# 2_disp.net
KiCad netlist of a schematic drawn in EAGLE
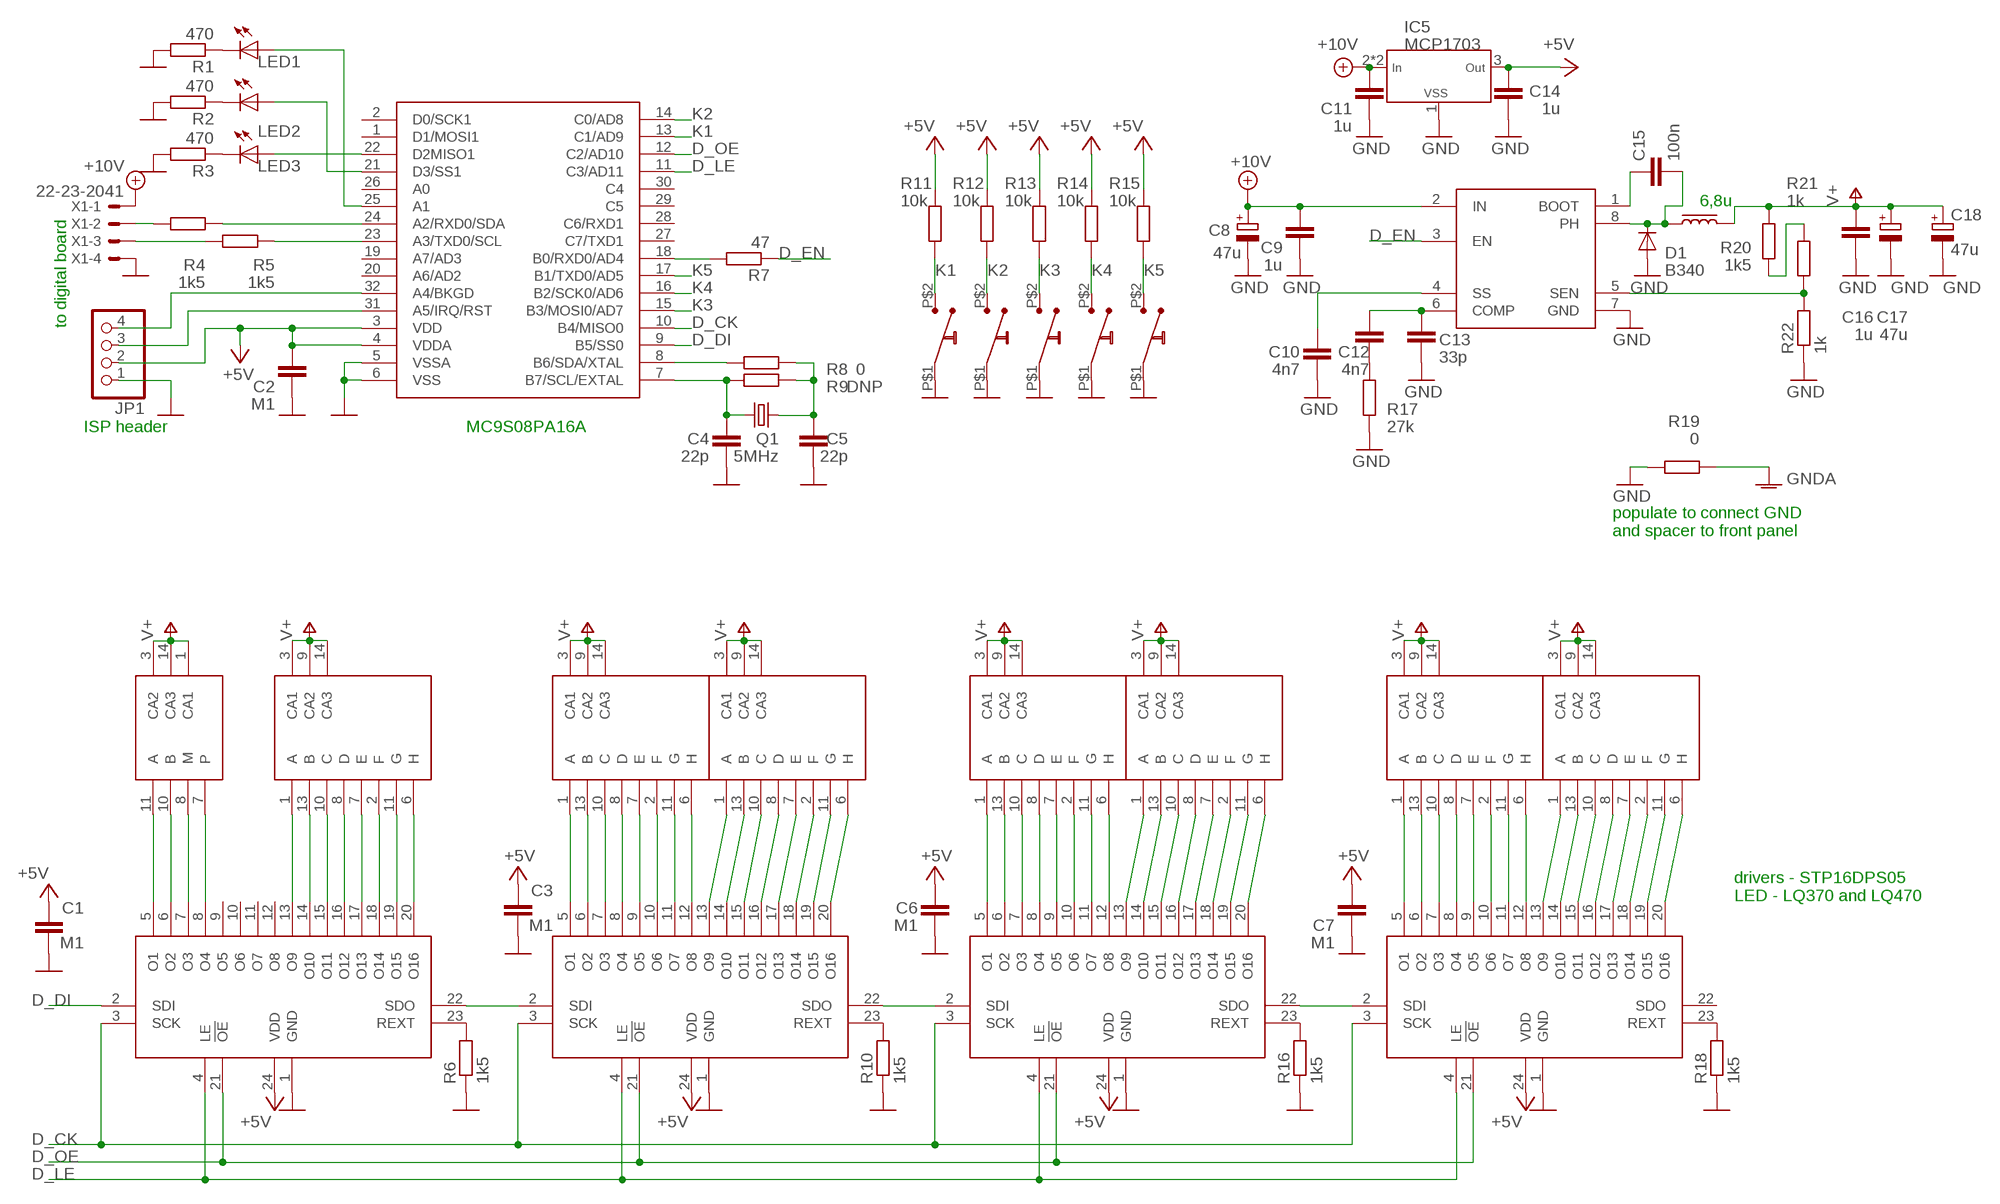
[diagram p0: schematic, sheet 1]

(export (version "E")
  (design (tool "Eeschema 10.0.6"))
  (components
    (comp (ref "C1")
      (value "M1")
      (footprint "eagle-import:R0805")
      (libsource (lib "eagle-import") (part "C_0806"))
    )
    (comp (ref "C2")
      (value "M1")
      (footprint "eagle-import:R0805")
      (libsource (lib "eagle-import") (part "C_0806"))
    )
    (comp (ref "C3")
      (value "M1")
      (footprint "eagle-import:R0805")
      (libsource (lib "eagle-import") (part "C_0806"))
    )
    (comp (ref "C4")
      (value "22p")
      (footprint "eagle-import:R0805")
      (libsource (lib "eagle-import") (part "C_0806"))
    )
    (comp (ref "C5")
      (value "22p")
      (footprint "eagle-import:R0805")
      (libsource (lib "eagle-import") (part "C_0806"))
    )
    (comp (ref "C6")
      (value "M1")
      (footprint "eagle-import:R0805")
      (libsource (lib "eagle-import") (part "C_0806"))
    )
    (comp (ref "C7")
      (value "M1")
      (footprint "eagle-import:R0805")
      (libsource (lib "eagle-import") (part "C_0806"))
    )
    (comp (ref "C8")
      (value "47u")
      (footprint "eagle-import:SMC_C")
      (libsource (lib "eagle-import") (part "CPOL-EUSMCC"))
    )
    (comp (ref "C9")
      (value "1u")
      (footprint "eagle-import:R0805")
      (libsource (lib "eagle-import") (part "C_0806"))
    )
    (comp (ref "C10")
      (value "4n7")
      (footprint "eagle-import:R0805")
      (libsource (lib "eagle-import") (part "C_0806"))
    )
    (comp (ref "C11")
      (value "1u")
      (footprint "eagle-import:R0805")
      (libsource (lib "eagle-import") (part "C_0806"))
    )
    (comp (ref "C12")
      (value "4n7")
      (footprint "eagle-import:R0805")
      (libsource (lib "eagle-import") (part "C_0806"))
    )
    (comp (ref "C13")
      (value "33p")
      (footprint "eagle-import:R0805")
      (libsource (lib "eagle-import") (part "C_0806"))
    )
    (comp (ref "C14")
      (value "1u")
      (footprint "eagle-import:R0805")
      (libsource (lib "eagle-import") (part "C_0806"))
    )
    (comp (ref "C15")
      (value "100n")
      (footprint "eagle-import:R0805")
      (libsource (lib "eagle-import") (part "C_0806"))
    )
    (comp (ref "C16")
      (value "1u")
      (footprint "eagle-import:R0805")
      (libsource (lib "eagle-import") (part "C_0806"))
    )
    (comp (ref "C17")
      (value "47u")
      (footprint "eagle-import:SMC_C")
      (libsource (lib "eagle-import") (part "CPOL-EUSMCC"))
    )
    (comp (ref "C18")
      (value "47u")
      (footprint "eagle-import:SMC_C")
      (libsource (lib "eagle-import") (part "CPOL-EUSMCC"))
    )
    (comp (ref "D1")
      (value "B340")
      (footprint "eagle-import:SMB")
      (libsource (lib "eagle-import") (part "DIODE-SMB"))
    )
    (comp (ref "DI1")
      (value "LQ3XX")
      (footprint "eagle-import:LQ_DISP")
      (libsource (lib "eagle-import") (part "LQ3XX"))
    )
    (comp (ref "DI2")
      (value "LQ4XX")
      (footprint "eagle-import:LQ_DISP")
      (libsource (lib "eagle-import") (part "LQ4XX"))
    )
    (comp (ref "DI3")
      (value "LQ4XX")
      (footprint "eagle-import:LQ_DISP")
      (libsource (lib "eagle-import") (part "LQ4XX"))
    )
    (comp (ref "DI4")
      (value "LQ4XX")
      (footprint "eagle-import:LQ_DISP")
      (libsource (lib "eagle-import") (part "LQ4XX"))
    )
    (comp (ref "DI5")
      (value "LQ4XX")
      (footprint "eagle-import:LQ_DISP")
      (libsource (lib "eagle-import") (part "LQ4XX"))
    )
    (comp (ref "DI6")
      (value "LQ4XX")
      (footprint "eagle-import:LQ_DISP")
      (libsource (lib "eagle-import") (part "LQ4XX"))
    )
    (comp (ref "DI7")
      (value "LQ4XX")
      (footprint "eagle-import:LQ_DISP")
      (libsource (lib "eagle-import") (part "LQ4XX"))
    )
    (comp (ref "DI8")
      (value "LQ4XX")
      (footprint "eagle-import:LQ_DISP")
      (libsource (lib "eagle-import") (part "LQ4XX"))
    )
    (comp (ref "IC1")
      (value "STP16CPS05")
      (footprint "eagle-import:QSOP24")
      (libsource (lib "eagle-import") (part "STP16CPS05"))
    )
    (comp (ref "IC2")
      (value "MC9S08PT60TQ32")
      (footprint "eagle-import:TQFP32-8")
      (libsource (lib "eagle-import") (part "MC9S08PT60TQ32"))
    )
    (comp (ref "IC3")
      (value "STP16CPS05")
      (footprint "eagle-import:QSOP24")
      (libsource (lib "eagle-import") (part "STP16CPS05"))
    )
    (comp (ref "IC4")
      (value "STP16CPS05")
      (footprint "eagle-import:QSOP24")
      (libsource (lib "eagle-import") (part "STP16CPS05"))
    )
    (comp (ref "IC5")
      (value "MCP1703")
      (footprint "eagle-import:SOT89")
      (libsource (lib "eagle-import") (part "MCP1702-SOT89"))
    )
    (comp (ref "IC6")
      (value "STP16CPS05")
      (footprint "eagle-import:QSOP24")
      (libsource (lib "eagle-import") (part "STP16CPS05"))
    )
    (comp (ref "IC7")
      (value "TPS54331")
      (footprint "eagle-import:SO-08")
      (libsource (lib "eagle-import") (part "TPS54331"))
    )
    (comp (ref "JP1")
      (value "PINHD-1X04_2.54")
      (footprint "eagle-import:1X04")
      (libsource (lib "eagle-import") (part "PINHD-1X04_2.54"))
    )
    (comp (ref "K1")
      (value "SWITCH_MINI6450")
      (footprint "eagle-import:SWITCH_6450")
      (libsource (lib "eagle-import") (part "SWITCH_MINI6450"))
    )
    (comp (ref "K2")
      (value "SWITCH_MINI6450")
      (footprint "eagle-import:SWITCH_6450")
      (libsource (lib "eagle-import") (part "SWITCH_MINI6450"))
    )
    (comp (ref "K3")
      (value "SWITCH_MINI6450")
      (footprint "eagle-import:SWITCH_6450")
      (libsource (lib "eagle-import") (part "SWITCH_MINI6450"))
    )
    (comp (ref "K4")
      (value "SWITCH_MINI6450")
      (footprint "eagle-import:SWITCH_6450")
      (libsource (lib "eagle-import") (part "SWITCH_MINI6450"))
    )
    (comp (ref "K5")
      (value "SWITCH_MINI6450")
      (footprint "eagle-import:SWITCH_6450")
      (libsource (lib "eagle-import") (part "SWITCH_MINI6450"))
    )
    (comp (ref "L1")
      (value "SRP7030")
      (footprint "eagle-import:BOURNS_SRP7030")
      (libsource (lib "eagle-import") (part "INDUCTORBOURNS_SRP7030"))
    )
    (comp (ref "LED1")
      (value "LEDCHIPLED_0805")
      (footprint "eagle-import:CHIPLED_0805")
      (libsource (lib "eagle-import") (part "LEDCHIPLED_0805"))
    )
    (comp (ref "LED2")
      (value "LEDCHIPLED_1206")
      (footprint "eagle-import:CHIPLED_1206")
      (libsource (lib "eagle-import") (part "LEDCHIPLED_1206"))
    )
    (comp (ref "LED3")
      (value "LEDCHIPLED_1206")
      (footprint "eagle-import:CHIPLED_1206")
      (libsource (lib "eagle-import") (part "LEDCHIPLED_1206"))
    )
    (comp (ref "Q1")
      (value "5MHz")
      (footprint "eagle-import:TC38H")
      (libsource (lib "eagle-import") (part "CRYSTALTC38H"))
    )
    (comp (ref "R1")
      (value "470")
      (footprint "eagle-import:R0805")
      (libsource (lib "eagle-import") (part "R_0805"))
    )
    (comp (ref "R2")
      (value "470")
      (footprint "eagle-import:R0805")
      (libsource (lib "eagle-import") (part "R_0805"))
    )
    (comp (ref "R3")
      (value "470")
      (footprint "eagle-import:R0805")
      (libsource (lib "eagle-import") (part "R_0805"))
    )
    (comp (ref "R4")
      (value "1k5")
      (footprint "eagle-import:R0805")
      (libsource (lib "eagle-import") (part "R_0805"))
    )
    (comp (ref "R5")
      (value "1k5")
      (footprint "eagle-import:R0805")
      (libsource (lib "eagle-import") (part "R_0805"))
    )
    (comp (ref "R6")
      (value "1k5")
      (footprint "eagle-import:R0805")
      (libsource (lib "eagle-import") (part "R_0805"))
    )
    (comp (ref "R7")
      (value "47")
      (footprint "eagle-import:R0805")
      (libsource (lib "eagle-import") (part "R_0805"))
    )
    (comp (ref "R8")
      (value "0")
      (footprint "eagle-import:R0805")
      (libsource (lib "eagle-import") (part "R_0805"))
    )
    (comp (ref "R9")
      (value "DNP")
      (footprint "eagle-import:R0805")
      (libsource (lib "eagle-import") (part "R_0805"))
    )
    (comp (ref "R10")
      (value "1k5")
      (footprint "eagle-import:R0805")
      (libsource (lib "eagle-import") (part "R_0805"))
    )
    (comp (ref "R11")
      (value "10k")
      (footprint "eagle-import:R0805")
      (libsource (lib "eagle-import") (part "R_0805"))
    )
    (comp (ref "R12")
      (value "10k")
      (footprint "eagle-import:R0805")
      (libsource (lib "eagle-import") (part "R_0805"))
    )
    (comp (ref "R13")
      (value "10k")
      (footprint "eagle-import:R0805")
      (libsource (lib "eagle-import") (part "R_0805"))
    )
    (comp (ref "R14")
      (value "10k")
      (footprint "eagle-import:R0805")
      (libsource (lib "eagle-import") (part "R_0805"))
    )
    (comp (ref "R15")
      (value "10k")
      (footprint "eagle-import:R0805")
      (libsource (lib "eagle-import") (part "R_0805"))
    )
    (comp (ref "R16")
      (value "1k5")
      (footprint "eagle-import:R0805")
      (libsource (lib "eagle-import") (part "R_0805"))
    )
    (comp (ref "R17")
      (value "27k")
      (footprint "eagle-import:R0805")
      (libsource (lib "eagle-import") (part "R_0805"))
    )
    (comp (ref "R18")
      (value "1k5")
      (footprint "eagle-import:R0805")
      (libsource (lib "eagle-import") (part "R_0805"))
    )
    (comp (ref "R19")
      (value "0")
      (footprint "eagle-import:R0805")
      (libsource (lib "eagle-import") (part "R_0805"))
    )
    (comp (ref "R20")
      (value "1k5")
      (footprint "eagle-import:R0805")
      (libsource (lib "eagle-import") (part "R_0805"))
    )
    (comp (ref "R21")
      (value "1k")
      (footprint "eagle-import:R0805")
      (libsource (lib "eagle-import") (part "R_0805"))
    )
    (comp (ref "R22")
      (value "1k")
      (footprint "eagle-import:R0805")
      (libsource (lib "eagle-import") (part "R_0805"))
    )
    (comp (ref "X1")
      (value "22-23-2041")
      (footprint "eagle-import:22-23-2041")
      (fields (field (name "MF") "MOLEX"))
      (libsource (lib "eagle-import") (part "22-23-2041"))
    )
  )
  (nets
    (net (code "1") (name "+5V") (class "Default")
      (node (ref "C1") (pin "2") (pinfunction "2_2") (pintype "passive"))
      (node (ref "C14") (pin "2") (pinfunction "2_2") (pintype "passive"))
      (node (ref "C2") (pin "2") (pinfunction "2_2") (pintype "passive"))
      (node (ref "C3") (pin "2") (pinfunction "2_2") (pintype "passive"))
      (node (ref "C6") (pin "2") (pinfunction "2_2") (pintype "passive"))
      (node (ref "C7") (pin "2") (pinfunction "2_2") (pintype "passive"))
      (node (ref "IC1") (pin "24") (pinfunction "VDD_24") (pintype "bidirectional"))
      (node (ref "IC2") (pin "3") (pinfunction "VDD_3") (pintype "bidirectional"))
      (node (ref "IC2") (pin "4") (pinfunction "VDDA_4") (pintype "bidirectional"))
      (node (ref "IC3") (pin "24") (pinfunction "VDD_24") (pintype "bidirectional"))
      (node (ref "IC4") (pin "24") (pinfunction "VDD_24") (pintype "bidirectional"))
      (node (ref "IC5") (pin "3") (pinfunction "OUT_3") (pintype "output"))
      (node (ref "IC6") (pin "24") (pinfunction "VDD_24") (pintype "bidirectional"))
      (node (ref "JP1") (pin "2") (pinfunction "2_2") (pintype "passive"))
      (node (ref "R11") (pin "1") (pinfunction "1_1") (pintype "passive"))
      (node (ref "R12") (pin "1") (pinfunction "1_1") (pintype "passive"))
      (node (ref "R13") (pin "1") (pinfunction "1_1") (pintype "passive"))
      (node (ref "R14") (pin "1") (pinfunction "1_1") (pintype "passive"))
      (node (ref "R15") (pin "1") (pinfunction "1_1") (pintype "passive"))
    )
    (net (code "2") (name "+10V") (class "Default")
      (node (ref "C11") (pin "2") (pinfunction "2_2") (pintype "passive"))
      (node (ref "C8") (pin "+") (pinfunction "+_+") (pintype "passive"))
      (node (ref "C9") (pin "2") (pinfunction "2_2") (pintype "passive"))
      (node (ref "IC5") (pin "2") (pinfunction "IN_2") (pintype "input"))
      (node (ref "IC5") (pin "2@1") (pinfunction "IN_2@1") (pintype "input"))
      (node (ref "IC7") (pin "2") (pinfunction "IN_2") (pintype "bidirectional"))
      (node (ref "X1") (pin "1") (pinfunction "S_1") (pintype "passive"))
    )
    (net (code "3") (name "/D_CK") (class "Default")
      (node (ref "IC1") (pin "3") (pinfunction "SCK_3") (pintype "bidirectional"))
      (node (ref "IC2") (pin "10") (pinfunction "B4/MISO0_10") (pintype "bidirectional"))
      (node (ref "IC3") (pin "3") (pinfunction "SCK_3") (pintype "bidirectional"))
      (node (ref "IC4") (pin "3") (pinfunction "SCK_3") (pintype "bidirectional"))
      (node (ref "IC6") (pin "3") (pinfunction "SCK_3") (pintype "bidirectional"))
    )
    (net (code "4") (name "/D_DI") (class "Default")
      (node (ref "IC1") (pin "2") (pinfunction "SDI_2") (pintype "bidirectional"))
      (node (ref "IC2") (pin "9") (pinfunction "B5/SS0_9") (pintype "bidirectional"))
    )
    (net (code "5") (name "/D_EN") (class "Default")
      (node (ref "IC7") (pin "3") (pinfunction "EN_3") (pintype "bidirectional"))
      (node (ref "R7") (pin "1") (pinfunction "1_1") (pintype "passive"))
    )
    (net (code "6") (name "/D_LE") (class "Default")
      (node (ref "IC1") (pin "4") (pinfunction "LE_4") (pintype "bidirectional"))
      (node (ref "IC2") (pin "11") (pinfunction "C3/AD11_11") (pintype "bidirectional"))
      (node (ref "IC3") (pin "4") (pinfunction "LE_4") (pintype "bidirectional"))
      (node (ref "IC4") (pin "4") (pinfunction "LE_4") (pintype "bidirectional"))
      (node (ref "IC6") (pin "4") (pinfunction "LE_4") (pintype "bidirectional"))
    )
    (net (code "7") (name "/D_OE") (class "Default")
      (node (ref "IC1") (pin "21") (pinfunction "~{OE}_21") (pintype "bidirectional"))
      (node (ref "IC2") (pin "12") (pinfunction "C2/AD10_12") (pintype "bidirectional"))
      (node (ref "IC3") (pin "21") (pinfunction "~{OE}_21") (pintype "bidirectional"))
      (node (ref "IC4") (pin "21") (pinfunction "~{OE}_21") (pintype "bidirectional"))
      (node (ref "IC6") (pin "21") (pinfunction "~{OE}_21") (pintype "bidirectional"))
    )
    (net (code "8") (name "/K1") (class "Default")
      (node (ref "IC2") (pin "13") (pinfunction "C1/AD9_13") (pintype "bidirectional"))
      (node (ref "K1") (pin "P$2") (pinfunction "P$2_P$2") (pintype "bidirectional"))
      (node (ref "R11") (pin "2") (pinfunction "2_2") (pintype "passive"))
    )
    (net (code "9") (name "/K2") (class "Default")
      (node (ref "IC2") (pin "14") (pinfunction "C0/AD8_14") (pintype "bidirectional"))
      (node (ref "K2") (pin "P$2") (pinfunction "P$2_P$2") (pintype "bidirectional"))
      (node (ref "R12") (pin "2") (pinfunction "2_2") (pintype "passive"))
    )
    (net (code "10") (name "/K3") (class "Default")
      (node (ref "IC2") (pin "15") (pinfunction "B3/MOSI0/AD7_15") (pintype "bidirectional"))
      (node (ref "K3") (pin "P$2") (pinfunction "P$2_P$2") (pintype "bidirectional"))
      (node (ref "R13") (pin "2") (pinfunction "2_2") (pintype "passive"))
    )
    (net (code "11") (name "/K4") (class "Default")
      (node (ref "IC2") (pin "16") (pinfunction "B2/SCK0/AD6_16") (pintype "bidirectional"))
      (node (ref "K4") (pin "P$2") (pinfunction "P$2_P$2") (pintype "bidirectional"))
      (node (ref "R14") (pin "2") (pinfunction "2_2") (pintype "passive"))
    )
    (net (code "12") (name "/K5") (class "Default")
      (node (ref "IC2") (pin "17") (pinfunction "B1/TXD0/AD5_17") (pintype "bidirectional"))
      (node (ref "K5") (pin "P$2") (pinfunction "P$2_P$2") (pintype "bidirectional"))
      (node (ref "R15") (pin "2") (pinfunction "2_2") (pintype "passive"))
    )
    (net (code "13") (name "GND") (class "Default")
      (node (ref "C1") (pin "1") (pinfunction "1_1") (pintype "passive"))
      (node (ref "C10") (pin "1") (pinfunction "1_1") (pintype "passive"))
      (node (ref "C11") (pin "1") (pinfunction "1_1") (pintype "passive"))
      (node (ref "C13") (pin "1") (pinfunction "1_1") (pintype "passive"))
      (node (ref "C14") (pin "1") (pinfunction "1_1") (pintype "passive"))
      (node (ref "C16") (pin "1") (pinfunction "1_1") (pintype "passive"))
      (node (ref "C17") (pin "-") (pinfunction "-_-") (pintype "passive"))
      (node (ref "C18") (pin "-") (pinfunction "-_-") (pintype "passive"))
      (node (ref "C2") (pin "1") (pinfunction "1_1") (pintype "passive"))
      (node (ref "C3") (pin "1") (pinfunction "1_1") (pintype "passive"))
      (node (ref "C4") (pin "1") (pinfunction "1_1") (pintype "passive"))
      (node (ref "C5") (pin "1") (pinfunction "1_1") (pintype "passive"))
      (node (ref "C6") (pin "1") (pinfunction "1_1") (pintype "passive"))
      (node (ref "C7") (pin "1") (pinfunction "1_1") (pintype "passive"))
      (node (ref "C8") (pin "-") (pinfunction "-_-") (pintype "passive"))
      (node (ref "C9") (pin "1") (pinfunction "1_1") (pintype "passive"))
      (node (ref "D1") (pin "A") (pinfunction "A_A") (pintype "passive"))
      (node (ref "IC1") (pin "1") (pinfunction "GND_1") (pintype "bidirectional"))
      (node (ref "IC2") (pin "5") (pinfunction "VSSA_5") (pintype "bidirectional"))
      (node (ref "IC2") (pin "6") (pinfunction "VSS_6") (pintype "bidirectional"))
      (node (ref "IC3") (pin "1") (pinfunction "GND_1") (pintype "bidirectional"))
      (node (ref "IC4") (pin "1") (pinfunction "GND_1") (pintype "bidirectional"))
      (node (ref "IC5") (pin "1") (pinfunction "VSS_1") (pintype "input"))
      (node (ref "IC6") (pin "1") (pinfunction "GND_1") (pintype "bidirectional"))
      (node (ref "IC7") (pin "7") (pinfunction "GND_7") (pintype "bidirectional"))
      (node (ref "JP1") (pin "1") (pinfunction "1_1") (pintype "passive"))
      (node (ref "K1") (pin "P$1") (pinfunction "P$1_P$1") (pintype "bidirectional"))
      (node (ref "K2") (pin "P$1") (pinfunction "P$1_P$1") (pintype "bidirectional"))
      (node (ref "K3") (pin "P$1") (pinfunction "P$1_P$1") (pintype "bidirectional"))
      (node (ref "K4") (pin "P$1") (pinfunction "P$1_P$1") (pintype "bidirectional"))
      (node (ref "K5") (pin "P$1") (pinfunction "P$1_P$1") (pintype "bidirectional"))
      (node (ref "R1") (pin "2") (pinfunction "2_2") (pintype "passive"))
      (node (ref "R10") (pin "1") (pinfunction "1_1") (pintype "passive"))
      (node (ref "R16") (pin "1") (pinfunction "1_1") (pintype "passive"))
      (node (ref "R17") (pin "1") (pinfunction "1_1") (pintype "passive"))
      (node (ref "R18") (pin "1") (pinfunction "1_1") (pintype "passive"))
      (node (ref "R19") (pin "2") (pinfunction "2_2") (pintype "passive"))
      (node (ref "R2") (pin "2") (pinfunction "2_2") (pintype "passive"))
      (node (ref "R22") (pin "1") (pinfunction "1_1") (pintype "passive"))
      (node (ref "R3") (pin "2") (pinfunction "2_2") (pintype "passive"))
      (node (ref "R6") (pin "1") (pinfunction "1_1") (pintype "passive"))
      (node (ref "X1") (pin "4") (pinfunction "S_4") (pintype "passive"))
    )
    (net (code "14") (name "GNDA") (class "Default")
      (node (ref "R19") (pin "1") (pinfunction "1_1") (pintype "passive"))
    )
    (net (code "15") (name "Net-(C5-Pad2)") (class "Default")
      (node (ref "C5") (pin "2") (pinfunction "2_2") (pintype "passive"))
      (node (ref "Q1") (pin "1") (pinfunction "1_1") (pintype "passive"))
      (node (ref "R8") (pin "1") (pinfunction "1_1") (pintype "passive"))
      (node (ref "R9") (pin "1") (pinfunction "1_1") (pintype "passive"))
    )
    (net (code "16") (name "Net-(C12-Pad1)") (class "Default")
      (node (ref "C12") (pin "1") (pinfunction "1_1") (pintype "passive"))
      (node (ref "R17") (pin "2") (pinfunction "2_2") (pintype "passive"))
    )
    (net (code "17") (name "Net-(DI1-A)") (class "Default")
      (node (ref "DI1") (pin "11") (pinfunction "A_11") (pintype "bidirectional"))
      (node (ref "IC1") (pin "5") (pinfunction "O1_5") (pintype "bidirectional"))
    )
    (net (code "18") (name "Net-(DI1-B)") (class "Default")
      (node (ref "DI1") (pin "10") (pinfunction "B_10") (pintype "bidirectional"))
      (node (ref "IC1") (pin "6") (pinfunction "O2_6") (pintype "bidirectional"))
    )
    (net (code "19") (name "Net-(DI1-M)") (class "Default")
      (node (ref "DI1") (pin "8") (pinfunction "M_8") (pintype "bidirectional"))
      (node (ref "IC1") (pin "7") (pinfunction "O3_7") (pintype "bidirectional"))
    )
    (net (code "20") (name "Net-(DI1-P)") (class "Default")
      (node (ref "DI1") (pin "7") (pinfunction "P_7") (pintype "bidirectional"))
      (node (ref "IC1") (pin "8") (pinfunction "O4_8") (pintype "bidirectional"))
    )
    (net (code "21") (name "Net-(DI2-A)") (class "Default")
      (node (ref "DI2") (pin "1") (pinfunction "A_1") (pintype "bidirectional"))
      (node (ref "IC1") (pin "13") (pinfunction "O9_13") (pintype "bidirectional"))
    )
    (net (code "22") (name "Net-(DI2-B)") (class "Default")
      (node (ref "DI2") (pin "13") (pinfunction "B_13") (pintype "bidirectional"))
      (node (ref "IC1") (pin "14") (pinfunction "O10_14") (pintype "bidirectional"))
    )
    (net (code "23") (name "Net-(DI2-C)") (class "Default")
      (node (ref "DI2") (pin "10") (pinfunction "C_10") (pintype "bidirectional"))
      (node (ref "IC1") (pin "15") (pinfunction "O11_15") (pintype "bidirectional"))
    )
    (net (code "24") (name "Net-(DI2-D)") (class "Default")
      (node (ref "DI2") (pin "8") (pinfunction "D_8") (pintype "bidirectional"))
      (node (ref "IC1") (pin "16") (pinfunction "O12_16") (pintype "bidirectional"))
    )
    (net (code "25") (name "Net-(DI2-E)") (class "Default")
      (node (ref "DI2") (pin "7") (pinfunction "E_7") (pintype "bidirectional"))
      (node (ref "IC1") (pin "17") (pinfunction "O13_17") (pintype "bidirectional"))
    )
    (net (code "26") (name "Net-(DI2-F)") (class "Default")
      (node (ref "DI2") (pin "2") (pinfunction "F_2") (pintype "bidirectional"))
      (node (ref "IC1") (pin "18") (pinfunction "O14_18") (pintype "bidirectional"))
    )
    (net (code "27") (name "Net-(DI2-G)") (class "Default")
      (node (ref "DI2") (pin "11") (pinfunction "G_11") (pintype "bidirectional"))
      (node (ref "IC1") (pin "19") (pinfunction "O15_19") (pintype "bidirectional"))
    )
    (net (code "28") (name "Net-(DI2-H)") (class "Default")
      (node (ref "DI2") (pin "6") (pinfunction "H_6") (pintype "bidirectional"))
      (node (ref "IC1") (pin "20") (pinfunction "O16_20") (pintype "bidirectional"))
    )
    (net (code "29") (name "Net-(DI3-A)") (class "Default")
      (node (ref "DI3") (pin "1") (pinfunction "A_1") (pintype "bidirectional"))
      (node (ref "IC3") (pin "5") (pinfunction "O1_5") (pintype "bidirectional"))
    )
    (net (code "30") (name "Net-(DI3-B)") (class "Default")
      (node (ref "DI3") (pin "13") (pinfunction "B_13") (pintype "bidirectional"))
      (node (ref "IC3") (pin "6") (pinfunction "O2_6") (pintype "bidirectional"))
    )
    (net (code "31") (name "Net-(DI3-C)") (class "Default")
      (node (ref "DI3") (pin "10") (pinfunction "C_10") (pintype "bidirectional"))
      (node (ref "IC3") (pin "7") (pinfunction "O3_7") (pintype "bidirectional"))
    )
    (net (code "32") (name "Net-(DI3-D)") (class "Default")
      (node (ref "DI3") (pin "8") (pinfunction "D_8") (pintype "bidirectional"))
      (node (ref "IC3") (pin "8") (pinfunction "O4_8") (pintype "bidirectional"))
    )
    (net (code "33") (name "Net-(DI3-E)") (class "Default")
      (node (ref "DI3") (pin "7") (pinfunction "E_7") (pintype "bidirectional"))
      (node (ref "IC3") (pin "9") (pinfunction "O5_9") (pintype "bidirectional"))
    )
    (net (code "34") (name "Net-(DI3-F)") (class "Default")
      (node (ref "DI3") (pin "2") (pinfunction "F_2") (pintype "bidirectional"))
      (node (ref "IC3") (pin "10") (pinfunction "O6_10") (pintype "bidirectional"))
    )
    (net (code "35") (name "Net-(DI3-G)") (class "Default")
      (node (ref "DI3") (pin "11") (pinfunction "G_11") (pintype "bidirectional"))
      (node (ref "IC3") (pin "11") (pinfunction "O7_11") (pintype "bidirectional"))
    )
    (net (code "36") (name "Net-(DI3-H)") (class "Default")
      (node (ref "DI3") (pin "6") (pinfunction "H_6") (pintype "bidirectional"))
      (node (ref "IC3") (pin "12") (pinfunction "O8_12") (pintype "bidirectional"))
    )
    (net (code "37") (name "Net-(DI4-A)") (class "Default")
      (node (ref "DI4") (pin "1") (pinfunction "A_1") (pintype "bidirectional"))
      (node (ref "IC3") (pin "13") (pinfunction "O9_13") (pintype "bidirectional"))
    )
    (net (code "38") (name "Net-(DI4-B)") (class "Default")
      (node (ref "DI4") (pin "13") (pinfunction "B_13") (pintype "bidirectional"))
      (node (ref "IC3") (pin "14") (pinfunction "O10_14") (pintype "bidirectional"))
    )
    (net (code "39") (name "Net-(DI4-C)") (class "Default")
      (node (ref "DI4") (pin "10") (pinfunction "C_10") (pintype "bidirectional"))
      (node (ref "IC3") (pin "15") (pinfunction "O11_15") (pintype "bidirectional"))
    )
    (net (code "40") (name "Net-(DI4-D)") (class "Default")
      (node (ref "DI4") (pin "8") (pinfunction "D_8") (pintype "bidirectional"))
      (node (ref "IC3") (pin "16") (pinfunction "O12_16") (pintype "bidirectional"))
    )
    (net (code "41") (name "Net-(DI4-E)") (class "Default")
      (node (ref "DI4") (pin "7") (pinfunction "E_7") (pintype "bidirectional"))
      (node (ref "IC3") (pin "17") (pinfunction "O13_17") (pintype "bidirectional"))
    )
    (net (code "42") (name "Net-(DI4-F)") (class "Default")
      (node (ref "DI4") (pin "2") (pinfunction "F_2") (pintype "bidirectional"))
      (node (ref "IC3") (pin "18") (pinfunction "O14_18") (pintype "bidirectional"))
    )
    (net (code "43") (name "Net-(DI4-G)") (class "Default")
      (node (ref "DI4") (pin "11") (pinfunction "G_11") (pintype "bidirectional"))
      (node (ref "IC3") (pin "19") (pinfunction "O15_19") (pintype "bidirectional"))
    )
    (net (code "44") (name "Net-(DI4-H)") (class "Default")
      (node (ref "DI4") (pin "6") (pinfunction "H_6") (pintype "bidirectional"))
      (node (ref "IC3") (pin "20") (pinfunction "O16_20") (pintype "bidirectional"))
    )
    (net (code "45") (name "Net-(DI5-A)") (class "Default")
      (node (ref "DI5") (pin "1") (pinfunction "A_1") (pintype "bidirectional"))
      (node (ref "IC4") (pin "5") (pinfunction "O1_5") (pintype "bidirectional"))
    )
    (net (code "46") (name "Net-(DI5-B)") (class "Default")
      (node (ref "DI5") (pin "13") (pinfunction "B_13") (pintype "bidirectional"))
      (node (ref "IC4") (pin "6") (pinfunction "O2_6") (pintype "bidirectional"))
    )
    (net (code "47") (name "Net-(DI5-C)") (class "Default")
      (node (ref "DI5") (pin "10") (pinfunction "C_10") (pintype "bidirectional"))
      (node (ref "IC4") (pin "7") (pinfunction "O3_7") (pintype "bidirectional"))
    )
    (net (code "48") (name "Net-(DI5-D)") (class "Default")
      (node (ref "DI5") (pin "8") (pinfunction "D_8") (pintype "bidirectional"))
      (node (ref "IC4") (pin "8") (pinfunction "O4_8") (pintype "bidirectional"))
    )
    (net (code "49") (name "Net-(DI5-E)") (class "Default")
      (node (ref "DI5") (pin "7") (pinfunction "E_7") (pintype "bidirectional"))
      (node (ref "IC4") (pin "9") (pinfunction "O5_9") (pintype "bidirectional"))
    )
    (net (code "50") (name "Net-(DI5-F)") (class "Default")
      (node (ref "DI5") (pin "2") (pinfunction "F_2") (pintype "bidirectional"))
      (node (ref "IC4") (pin "10") (pinfunction "O6_10") (pintype "bidirectional"))
    )
    (net (code "51") (name "Net-(DI5-G)") (class "Default")
      (node (ref "DI5") (pin "11") (pinfunction "G_11") (pintype "bidirectional"))
      (node (ref "IC4") (pin "11") (pinfunction "O7_11") (pintype "bidirectional"))
    )
    (net (code "52") (name "Net-(DI5-H)") (class "Default")
      (node (ref "DI5") (pin "6") (pinfunction "H_6") (pintype "bidirectional"))
      (node (ref "IC4") (pin "12") (pinfunction "O8_12") (pintype "bidirectional"))
    )
    (net (code "53") (name "Net-(DI6-A)") (class "Default")
      (node (ref "DI6") (pin "1") (pinfunction "A_1") (pintype "bidirectional"))
      (node (ref "IC4") (pin "13") (pinfunction "O9_13") (pintype "bidirectional"))
    )
    (net (code "54") (name "Net-(DI6-B)") (class "Default")
      (node (ref "DI6") (pin "13") (pinfunction "B_13") (pintype "bidirectional"))
      (node (ref "IC4") (pin "14") (pinfunction "O10_14") (pintype "bidirectional"))
    )
    (net (code "55") (name "Net-(DI6-C)") (class "Default")
      (node (ref "DI6") (pin "10") (pinfunction "C_10") (pintype "bidirectional"))
      (node (ref "IC4") (pin "15") (pinfunction "O11_15") (pintype "bidirectional"))
    )
    (net (code "56") (name "Net-(DI6-D)") (class "Default")
      (node (ref "DI6") (pin "8") (pinfunction "D_8") (pintype "bidirectional"))
      (node (ref "IC4") (pin "16") (pinfunction "O12_16") (pintype "bidirectional"))
    )
    (net (code "57") (name "Net-(DI6-E)") (class "Default")
      (node (ref "DI6") (pin "7") (pinfunction "E_7") (pintype "bidirectional"))
      (node (ref "IC4") (pin "17") (pinfunction "O13_17") (pintype "bidirectional"))
    )
    (net (code "58") (name "Net-(DI6-F)") (class "Default")
      (node (ref "DI6") (pin "2") (pinfunction "F_2") (pintype "bidirectional"))
      (node (ref "IC4") (pin "18") (pinfunction "O14_18") (pintype "bidirectional"))
    )
    (net (code "59") (name "Net-(DI6-G)") (class "Default")
      (node (ref "DI6") (pin "11") (pinfunction "G_11") (pintype "bidirectional"))
      (node (ref "IC4") (pin "19") (pinfunction "O15_19") (pintype "bidirectional"))
    )
    (net (code "60") (name "Net-(DI6-H)") (class "Default")
      (node (ref "DI6") (pin "6") (pinfunction "H_6") (pintype "bidirectional"))
      (node (ref "IC4") (pin "20") (pinfunction "O16_20") (pintype "bidirectional"))
    )
    (net (code "61") (name "Net-(DI7-A)") (class "Default")
      (node (ref "DI7") (pin "1") (pinfunction "A_1") (pintype "bidirectional"))
      (node (ref "IC6") (pin "5") (pinfunction "O1_5") (pintype "bidirectional"))
    )
    (net (code "62") (name "Net-(DI7-B)") (class "Default")
      (node (ref "DI7") (pin "13") (pinfunction "B_13") (pintype "bidirectional"))
      (node (ref "IC6") (pin "6") (pinfunction "O2_6") (pintype "bidirectional"))
    )
    (net (code "63") (name "Net-(DI7-C)") (class "Default")
      (node (ref "DI7") (pin "10") (pinfunction "C_10") (pintype "bidirectional"))
      (node (ref "IC6") (pin "7") (pinfunction "O3_7") (pintype "bidirectional"))
    )
    (net (code "64") (name "Net-(DI7-D)") (class "Default")
      (node (ref "DI7") (pin "8") (pinfunction "D_8") (pintype "bidirectional"))
      (node (ref "IC6") (pin "8") (pinfunction "O4_8") (pintype "bidirectional"))
    )
    (net (code "65") (name "Net-(DI7-E)") (class "Default")
      (node (ref "DI7") (pin "7") (pinfunction "E_7") (pintype "bidirectional"))
      (node (ref "IC6") (pin "9") (pinfunction "O5_9") (pintype "bidirectional"))
    )
    (net (code "66") (name "Net-(DI7-F)") (class "Default")
      (node (ref "DI7") (pin "2") (pinfunction "F_2") (pintype "bidirectional"))
      (node (ref "IC6") (pin "10") (pinfunction "O6_10") (pintype "bidirectional"))
    )
    (net (code "67") (name "Net-(DI7-G)") (class "Default")
      (node (ref "DI7") (pin "11") (pinfunction "G_11") (pintype "bidirectional"))
      (node (ref "IC6") (pin "11") (pinfunction "O7_11") (pintype "bidirectional"))
    )
    (net (code "68") (name "Net-(DI7-H)") (class "Default")
      (node (ref "DI7") (pin "6") (pinfunction "H_6") (pintype "bidirectional"))
      (node (ref "IC6") (pin "12") (pinfunction "O8_12") (pintype "bidirectional"))
    )
    (net (code "69") (name "Net-(DI8-A)") (class "Default")
      (node (ref "DI8") (pin "1") (pinfunction "A_1") (pintype "bidirectional"))
      (node (ref "IC6") (pin "13") (pinfunction "O9_13") (pintype "bidirectional"))
    )
    (net (code "70") (name "Net-(DI8-B)") (class "Default")
      (node (ref "DI8") (pin "13") (pinfunction "B_13") (pintype "bidirectional"))
      (node (ref "IC6") (pin "14") (pinfunction "O10_14") (pintype "bidirectional"))
    )
    (net (code "71") (name "Net-(DI8-C)") (class "Default")
      (node (ref "DI8") (pin "10") (pinfunction "C_10") (pintype "bidirectional"))
      (node (ref "IC6") (pin "15") (pinfunction "O11_15") (pintype "bidirectional"))
    )
    (net (code "72") (name "Net-(DI8-D)") (class "Default")
      (node (ref "DI8") (pin "8") (pinfunction "D_8") (pintype "bidirectional"))
      (node (ref "IC6") (pin "16") (pinfunction "O12_16") (pintype "bidirectional"))
    )
    (net (code "73") (name "Net-(DI8-E)") (class "Default")
      (node (ref "DI8") (pin "7") (pinfunction "E_7") (pintype "bidirectional"))
      (node (ref "IC6") (pin "17") (pinfunction "O13_17") (pintype "bidirectional"))
    )
    (net (code "74") (name "Net-(DI8-F)") (class "Default")
      (node (ref "DI8") (pin "2") (pinfunction "F_2") (pintype "bidirectional"))
      (node (ref "IC6") (pin "18") (pinfunction "O14_18") (pintype "bidirectional"))
    )
    (net (code "75") (name "Net-(DI8-G)") (class "Default")
      (node (ref "DI8") (pin "11") (pinfunction "G_11") (pintype "bidirectional"))
      (node (ref "IC6") (pin "19") (pinfunction "O15_19") (pintype "bidirectional"))
    )
    (net (code "76") (name "Net-(DI8-H)") (class "Default")
      (node (ref "DI8") (pin "6") (pinfunction "H_6") (pintype "bidirectional"))
      (node (ref "IC6") (pin "20") (pinfunction "O16_20") (pintype "bidirectional"))
    )
    (net (code "77") (name "Net-(IC1-REXT)") (class "Default")
      (node (ref "IC1") (pin "23") (pinfunction "REXT_23") (pintype "bidirectional"))
      (node (ref "R6") (pin "2") (pinfunction "2_2") (pintype "passive"))
    )
    (net (code "78") (name "Net-(IC1-SDO)") (class "Default")
      (node (ref "IC1") (pin "22") (pinfunction "SDO_22") (pintype "bidirectional"))
      (node (ref "IC3") (pin "2") (pinfunction "SDI_2") (pintype "bidirectional"))
    )
    (net (code "79") (name "Net-(IC2-A1)") (class "Default")
      (node (ref "IC2") (pin "25") (pinfunction "A1_25") (pintype "bidirectional"))
      (node (ref "LED1") (pin "A") (pinfunction "A_A") (pintype "passive"))
    )
    (net (code "80") (name "Net-(IC2-A2{slash}RXD0{slash}SDA)") (class "Default")
      (node (ref "IC2") (pin "24") (pinfunction "A2/RXD0/SDA_24") (pintype "bidirectional"))
      (node (ref "R4") (pin "1") (pinfunction "1_1") (pintype "passive"))
    )
    (net (code "81") (name "Net-(IC2-A3{slash}TXD0{slash}SCL)") (class "Default")
      (node (ref "IC2") (pin "23") (pinfunction "A3/TXD0/SCL_23") (pintype "bidirectional"))
      (node (ref "R5") (pin "1") (pinfunction "1_1") (pintype "passive"))
    )
    (net (code "82") (name "Net-(IC2-A4{slash}BKGD)") (class "Default")
      (node (ref "IC2") (pin "32") (pinfunction "A4/BKGD_32") (pintype "bidirectional"))
      (node (ref "JP1") (pin "4") (pinfunction "4_4") (pintype "passive"))
    )
    (net (code "83") (name "Net-(IC2-A5{slash}IRQ{slash}RST)") (class "Default")
      (node (ref "IC2") (pin "31") (pinfunction "A5/IRQ/RST_31") (pintype "bidirectional"))
      (node (ref "JP1") (pin "3") (pinfunction "3_3") (pintype "passive"))
    )
    (net (code "84") (name "Net-(IC2-B0{slash}RXD0{slash}AD4)") (class "Default")
      (node (ref "IC2") (pin "18") (pinfunction "B0/RXD0/AD4_18") (pintype "bidirectional"))
      (node (ref "R7") (pin "2") (pinfunction "2_2") (pintype "passive"))
    )
    (net (code "85") (name "Net-(IC2-B6{slash}SDA{slash}XTAL)") (class "Default")
      (node (ref "IC2") (pin "8") (pinfunction "B6/SDA/XTAL_8") (pintype "bidirectional"))
      (node (ref "R8") (pin "2") (pinfunction "2_2") (pintype "passive"))
    )
    (net (code "86") (name "Net-(IC2-B7{slash}SCL{slash}EXTAL)") (class "Default")
      (node (ref "C4") (pin "2") (pinfunction "2_2") (pintype "passive"))
      (node (ref "IC2") (pin "7") (pinfunction "B7/SCL/EXTAL_7") (pintype "bidirectional"))
      (node (ref "Q1") (pin "2") (pinfunction "2_2") (pintype "passive"))
      (node (ref "R9") (pin "2") (pinfunction "2_2") (pintype "passive"))
    )
    (net (code "87") (name "Net-(IC2-D2MISO1)") (class "Default")
      (node (ref "IC2") (pin "22") (pinfunction "D2MISO1_22") (pintype "bidirectional"))
      (node (ref "LED3") (pin "A") (pinfunction "A_A") (pintype "passive"))
    )
    (net (code "88") (name "Net-(IC2-D3{slash}SS1)") (class "Default")
      (node (ref "IC2") (pin "21") (pinfunction "D3/SS1_21") (pintype "bidirectional"))
      (node (ref "LED2") (pin "A") (pinfunction "A_A") (pintype "passive"))
    )
    (net (code "89") (name "Net-(IC3-REXT)") (class "Default")
      (node (ref "IC3") (pin "23") (pinfunction "REXT_23") (pintype "bidirectional"))
      (node (ref "R10") (pin "2") (pinfunction "2_2") (pintype "passive"))
    )
    (net (code "90") (name "Net-(IC3-SDO)") (class "Default")
      (node (ref "IC3") (pin "22") (pinfunction "SDO_22") (pintype "bidirectional"))
      (node (ref "IC4") (pin "2") (pinfunction "SDI_2") (pintype "bidirectional"))
    )
    (net (code "91") (name "Net-(IC4-REXT)") (class "Default")
      (node (ref "IC4") (pin "23") (pinfunction "REXT_23") (pintype "bidirectional"))
      (node (ref "R16") (pin "2") (pinfunction "2_2") (pintype "passive"))
    )
    (net (code "92") (name "Net-(IC4-SDO)") (class "Default")
      (node (ref "IC4") (pin "22") (pinfunction "SDO_22") (pintype "bidirectional"))
      (node (ref "IC6") (pin "2") (pinfunction "SDI_2") (pintype "bidirectional"))
    )
    (net (code "93") (name "Net-(IC6-REXT)") (class "Default")
      (node (ref "IC6") (pin "23") (pinfunction "REXT_23") (pintype "bidirectional"))
      (node (ref "R18") (pin "2") (pinfunction "2_2") (pintype "passive"))
    )
    (net (code "94") (name "Net-(IC7-BOOT)") (class "Default")
      (node (ref "C15") (pin "1") (pinfunction "1_1") (pintype "passive"))
      (node (ref "IC7") (pin "1") (pinfunction "BOOT_1") (pintype "bidirectional"))
    )
    (net (code "95") (name "Net-(IC7-COMP)") (class "Default")
      (node (ref "C12") (pin "2") (pinfunction "2_2") (pintype "passive"))
      (node (ref "C13") (pin "2") (pinfunction "2_2") (pintype "passive"))
      (node (ref "IC7") (pin "6") (pinfunction "COMP_6") (pintype "bidirectional"))
    )
    (net (code "96") (name "Net-(IC7-PH)") (class "Default")
      (node (ref "C15") (pin "2") (pinfunction "2_2") (pintype "passive"))
      (node (ref "D1") (pin "C") (pinfunction "C_C") (pintype "passive"))
      (node (ref "IC7") (pin "8") (pinfunction "PH_8") (pintype "bidirectional"))
      (node (ref "L1") (pin "P$1") (pinfunction "P$1_P$1") (pintype "bidirectional"))
    )
    (net (code "97") (name "Net-(IC7-SEN)") (class "Default")
      (node (ref "IC7") (pin "5") (pinfunction "SEN_5") (pintype "bidirectional"))
      (node (ref "R21") (pin "1") (pinfunction "1_1") (pintype "passive"))
      (node (ref "R22") (pin "2") (pinfunction "2_2") (pintype "passive"))
    )
    (net (code "98") (name "Net-(IC7-SS)") (class "Default")
      (node (ref "C10") (pin "2") (pinfunction "2_2") (pintype "passive"))
      (node (ref "IC7") (pin "4") (pinfunction "SS_4") (pintype "bidirectional"))
    )
    (net (code "99") (name "Net-(LED1-PadC)") (class "Default")
      (node (ref "LED1") (pin "C") (pinfunction "C_C") (pintype "passive"))
      (node (ref "R1") (pin "1") (pinfunction "1_1") (pintype "passive"))
    )
    (net (code "100") (name "Net-(LED2-PadC)") (class "Default")
      (node (ref "LED2") (pin "C") (pinfunction "C_C") (pintype "passive"))
      (node (ref "R2") (pin "1") (pinfunction "1_1") (pintype "passive"))
    )
    (net (code "101") (name "Net-(LED3-PadC)") (class "Default")
      (node (ref "LED3") (pin "C") (pinfunction "C_C") (pintype "passive"))
      (node (ref "R3") (pin "1") (pinfunction "1_1") (pintype "passive"))
    )
    (net (code "102") (name "Net-(R20-Pad1)") (class "Default")
      (node (ref "R20") (pin "1") (pinfunction "1_1") (pintype "passive"))
      (node (ref "R21") (pin "2") (pinfunction "2_2") (pintype "passive"))
    )
    (net (code "103") (name "Net-(X1B-S)") (class "Default")
      (node (ref "R4") (pin "2") (pinfunction "2_2") (pintype "passive"))
      (node (ref "X1") (pin "2") (pinfunction "S_2") (pintype "passive"))
    )
    (net (code "104") (name "Net-(X1C-S)") (class "Default")
      (node (ref "R5") (pin "2") (pinfunction "2_2") (pintype "passive"))
      (node (ref "X1") (pin "3") (pinfunction "S_3") (pintype "passive"))
    )
    (net (code "105") (name "V+") (class "Default")
      (node (ref "C16") (pin "2") (pinfunction "2_2") (pintype "passive"))
      (node (ref "C17") (pin "+") (pinfunction "+_+") (pintype "passive"))
      (node (ref "C18") (pin "+") (pinfunction "+_+") (pintype "passive"))
      (node (ref "DI1") (pin "1") (pinfunction "CA1_1") (pintype "bidirectional"))
      (node (ref "DI1") (pin "14") (pinfunction "CA3_14") (pintype "bidirectional"))
      (node (ref "DI1") (pin "3") (pinfunction "CA2_3") (pintype "bidirectional"))
      (node (ref "DI2") (pin "14") (pinfunction "CA3_14") (pintype "bidirectional"))
      (node (ref "DI2") (pin "3") (pinfunction "CA1_3") (pintype "bidirectional"))
      (node (ref "DI2") (pin "9") (pinfunction "CA2_9") (pintype "bidirectional"))
      (node (ref "DI3") (pin "14") (pinfunction "CA3_14") (pintype "bidirectional"))
      (node (ref "DI3") (pin "3") (pinfunction "CA1_3") (pintype "bidirectional"))
      (node (ref "DI3") (pin "9") (pinfunction "CA2_9") (pintype "bidirectional"))
      (node (ref "DI4") (pin "14") (pinfunction "CA3_14") (pintype "bidirectional"))
      (node (ref "DI4") (pin "3") (pinfunction "CA1_3") (pintype "bidirectional"))
      (node (ref "DI4") (pin "9") (pinfunction "CA2_9") (pintype "bidirectional"))
      (node (ref "DI5") (pin "14") (pinfunction "CA3_14") (pintype "bidirectional"))
      (node (ref "DI5") (pin "3") (pinfunction "CA1_3") (pintype "bidirectional"))
      (node (ref "DI5") (pin "9") (pinfunction "CA2_9") (pintype "bidirectional"))
      (node (ref "DI6") (pin "14") (pinfunction "CA3_14") (pintype "bidirectional"))
      (node (ref "DI6") (pin "3") (pinfunction "CA1_3") (pintype "bidirectional"))
      (node (ref "DI6") (pin "9") (pinfunction "CA2_9") (pintype "bidirectional"))
      (node (ref "DI7") (pin "14") (pinfunction "CA3_14") (pintype "bidirectional"))
      (node (ref "DI7") (pin "3") (pinfunction "CA1_3") (pintype "bidirectional"))
      (node (ref "DI7") (pin "9") (pinfunction "CA2_9") (pintype "bidirectional"))
      (node (ref "DI8") (pin "14") (pinfunction "CA3_14") (pintype "bidirectional"))
      (node (ref "DI8") (pin "3") (pinfunction "CA1_3") (pintype "bidirectional"))
      (node (ref "DI8") (pin "9") (pinfunction "CA2_9") (pintype "bidirectional"))
      (node (ref "L1") (pin "P$2") (pinfunction "P$2_P$2") (pintype "bidirectional"))
      (node (ref "R20") (pin "2") (pinfunction "2_2") (pintype "passive"))
    )
    (net (code "106") (name "unconnected-(IC1-O5-Pad9)") (class "Default")
      (node (ref "IC1") (pin "9") (pinfunction "O5_9") (pintype "bidirectional"))
    )
    (net (code "107") (name "unconnected-(IC1-O6-Pad10)") (class "Default")
      (node (ref "IC1") (pin "10") (pinfunction "O6_10") (pintype "bidirectional"))
    )
    (net (code "108") (name "unconnected-(IC1-O7-Pad11)") (class "Default")
      (node (ref "IC1") (pin "11") (pinfunction "O7_11") (pintype "bidirectional"))
    )
    (net (code "109") (name "unconnected-(IC1-O8-Pad12)") (class "Default")
      (node (ref "IC1") (pin "12") (pinfunction "O8_12") (pintype "bidirectional"))
    )
    (net (code "110") (name "unconnected-(IC2-A0-Pad26)") (class "Default")
      (node (ref "IC2") (pin "26") (pinfunction "A0_26") (pintype "bidirectional"))
    )
    (net (code "111") (name "unconnected-(IC2-A6{slash}AD2-Pad20)") (class "Default")
      (node (ref "IC2") (pin "20") (pinfunction "A6/AD2_20") (pintype "bidirectional"))
    )
    (net (code "112") (name "unconnected-(IC2-A7{slash}AD3-Pad19)") (class "Default")
      (node (ref "IC2") (pin "19") (pinfunction "A7/AD3_19") (pintype "bidirectional"))
    )
    (net (code "113") (name "unconnected-(IC2-C4-Pad30)") (class "Default")
      (node (ref "IC2") (pin "30") (pinfunction "C4_30") (pintype "bidirectional"))
    )
    (net (code "114") (name "unconnected-(IC2-C5-Pad29)") (class "Default")
      (node (ref "IC2") (pin "29") (pinfunction "C5_29") (pintype "bidirectional"))
    )
    (net (code "115") (name "unconnected-(IC2-C6{slash}RXD1-Pad28)") (class "Default")
      (node (ref "IC2") (pin "28") (pinfunction "C6/RXD1_28") (pintype "bidirectional"))
    )
    (net (code "116") (name "unconnected-(IC2-C7{slash}TXD1-Pad27)") (class "Default")
      (node (ref "IC2") (pin "27") (pinfunction "C7/TXD1_27") (pintype "bidirectional"))
    )
    (net (code "117") (name "unconnected-(IC2-D0{slash}SCK1-Pad2)") (class "Default")
      (node (ref "IC2") (pin "2") (pinfunction "D0/SCK1_2") (pintype "bidirectional"))
    )
    (net (code "118") (name "unconnected-(IC2-D1{slash}MOSI1-Pad1)") (class "Default")
      (node (ref "IC2") (pin "1") (pinfunction "D1/MOSI1_1") (pintype "bidirectional"))
    )
    (net (code "119") (name "unconnected-(IC6-SDO-Pad22)") (class "Default")
      (node (ref "IC6") (pin "22") (pinfunction "SDO_22") (pintype "bidirectional"))
    )
  )
)
